# STM8L-FOX_80m_PA_V5_3.net
KiCad netlist of a schematic drawn in EAGLE
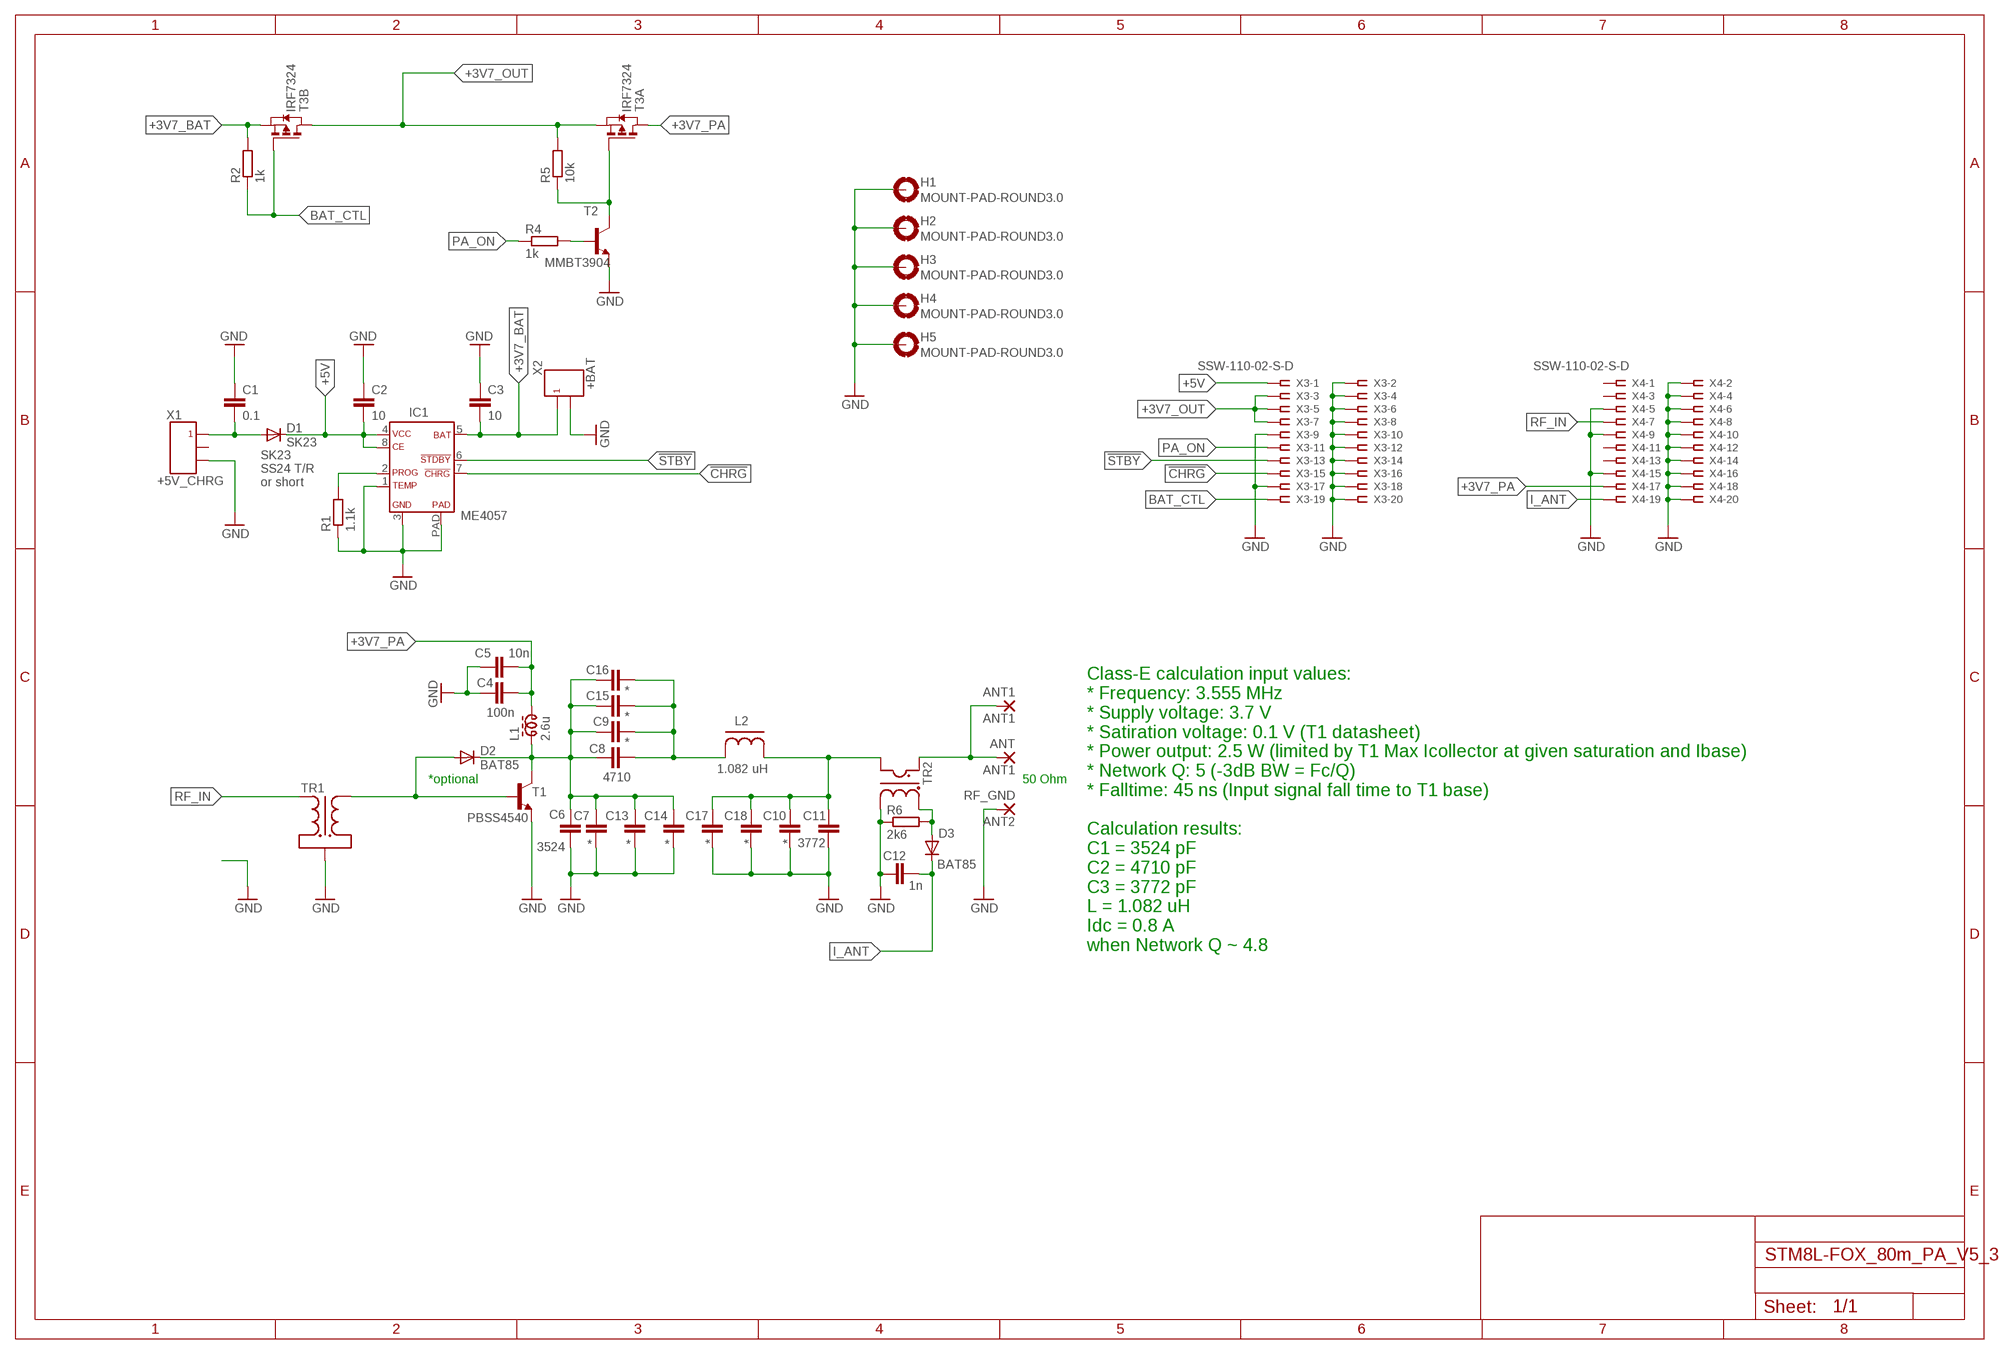
[diagram p0: schematic, sheet 1]

(export (version "E")
  (design (tool "Eeschema 10.0.6"))
  (components
    (comp (ref "ANT")
      (value "ANT1")
      (footprint "eagle-import:2,54_0,8")
      (libsource (lib "eagle-import") (part "WIREPAD2,54/0,8"))
    )
    (comp (ref "ANT1")
      (value "ANT1")
      (footprint "eagle-import:2,54_0,8")
      (libsource (lib "eagle-import") (part "WIREPAD2,54/0,8"))
    )
    (comp (ref "C1")
      (value "0.1")
      (footprint "eagle-import:C1206K")
      (libsource (lib "eagle-import") (part "C-EUC1206K"))
    )
    (comp (ref "C2")
      (value "10")
      (footprint "eagle-import:C1206K")
      (libsource (lib "eagle-import") (part "C-EUC1206K"))
    )
    (comp (ref "C3")
      (value "10")
      (footprint "eagle-import:C1206K")
      (libsource (lib "eagle-import") (part "C-EUC1206K"))
    )
    (comp (ref "C4")
      (value "100n")
      (footprint "eagle-import:C1206K")
      (libsource (lib "eagle-import") (part "C-EUC1206K"))
    )
    (comp (ref "C5")
      (value "10n")
      (footprint "eagle-import:C1206K")
      (libsource (lib "eagle-import") (part "C-EUC1206K"))
    )
    (comp (ref "C6")
      (value "3524")
      (footprint "eagle-import:C1206K")
      (libsource (lib "eagle-import") (part "C-EUC1206K"))
    )
    (comp (ref "C7")
      (value "*")
      (footprint "eagle-import:C1206K")
      (libsource (lib "eagle-import") (part "C-EUC1206K"))
    )
    (comp (ref "C8")
      (value "4710")
      (footprint "eagle-import:C1206K")
      (libsource (lib "eagle-import") (part "C-EUC1206K"))
    )
    (comp (ref "C9")
      (value "*")
      (footprint "eagle-import:C1206K")
      (libsource (lib "eagle-import") (part "C-EUC1206K"))
    )
    (comp (ref "C10")
      (value "*")
      (footprint "eagle-import:C1206K")
      (libsource (lib "eagle-import") (part "C-EUC1206K"))
    )
    (comp (ref "C11")
      (value "3772")
      (footprint "eagle-import:C1206K")
      (libsource (lib "eagle-import") (part "C-EUC1206K"))
    )
    (comp (ref "C12")
      (value "1n")
      (footprint "eagle-import:C1206K")
      (libsource (lib "eagle-import") (part "C-EUC1206K"))
    )
    (comp (ref "C13")
      (value "*")
      (footprint "eagle-import:C1206K")
      (libsource (lib "eagle-import") (part "C-EUC1206K"))
    )
    (comp (ref "C14")
      (value "*")
      (footprint "eagle-import:C1206K")
      (libsource (lib "eagle-import") (part "C-EUC1206K"))
    )
    (comp (ref "C15")
      (value "*")
      (footprint "eagle-import:C1206K")
      (libsource (lib "eagle-import") (part "C-EUC1206K"))
    )
    (comp (ref "C16")
      (value "*")
      (footprint "eagle-import:C1206K")
      (libsource (lib "eagle-import") (part "C-EUC1206K"))
    )
    (comp (ref "C17")
      (value "*")
      (footprint "eagle-import:C1206K")
      (libsource (lib "eagle-import") (part "C-EUC1206K"))
    )
    (comp (ref "C18")
      (value "*")
      (footprint "eagle-import:C1206K")
      (libsource (lib "eagle-import") (part "C-EUC1206K"))
    )
    (comp (ref "D1")
      (value "SK23")
      (footprint "eagle-import:DO-214AC")
      (libsource (lib "eagle-import") (part "DIODE-DO-214AC"))
    )
    (comp (ref "D2")
      (value "BAT85")
      (footprint "eagle-import:DO34-7")
      (libsource (lib "eagle-import") (part "BAT81"))
    )
    (comp (ref "D3")
      (value "BAT85")
      (footprint "eagle-import:DO34-7")
      (libsource (lib "eagle-import") (part "BAT81"))
    )
    (comp (ref "H1")
      (value "MOUNT-PAD-ROUND3.0")
      (footprint "eagle-import:3,0-PAD")
      (libsource (lib "eagle-import") (part "MOUNT-PAD-ROUND3.0"))
    )
    (comp (ref "H2")
      (value "MOUNT-PAD-ROUND3.0")
      (footprint "eagle-import:3,0-PAD")
      (libsource (lib "eagle-import") (part "MOUNT-PAD-ROUND3.0"))
    )
    (comp (ref "H3")
      (value "MOUNT-PAD-ROUND3.0")
      (footprint "eagle-import:3,0-PAD")
      (libsource (lib "eagle-import") (part "MOUNT-PAD-ROUND3.0"))
    )
    (comp (ref "H4")
      (value "MOUNT-PAD-ROUND3.0")
      (footprint "eagle-import:3,0-PAD")
      (libsource (lib "eagle-import") (part "MOUNT-PAD-ROUND3.0"))
    )
    (comp (ref "H5")
      (value "MOUNT-PAD-ROUND3.0")
      (footprint "eagle-import:3,0-PAD")
      (libsource (lib "eagle-import") (part "MOUNT-PAD-ROUND3.0"))
    )
    (comp (ref "IC1")
      (value "ME4057A")
      (footprint "eagle-import:SOP08-PP")
      (libsource (lib "eagle-import") (part "ME4057"))
    )
    (comp (ref "L1")
      (value "2.6u")
      (footprint "eagle-import:ZD6-3W")
      (libsource (lib "eagle-import") (part "ZD60820513"))
    )
    (comp (ref "L2")
      (value "1.082 uH")
      (footprint "eagle-import:T68_COIL")
      (libsource (lib "eagle-import") (part "T68_COIL"))
    )
    (comp (ref "R1")
      (value "1.1k")
      (footprint "eagle-import:R1206")
      (libsource (lib "eagle-import") (part "R-EU_R1206"))
    )
    (comp (ref "R2")
      (value "1k")
      (footprint "eagle-import:R1206")
      (libsource (lib "eagle-import") (part "R-EU_R1206"))
    )
    (comp (ref "R4")
      (value "1k")
      (footprint "eagle-import:R1206")
      (libsource (lib "eagle-import") (part "R-EU_R1206"))
    )
    (comp (ref "R5")
      (value "10k")
      (footprint "eagle-import:R1206")
      (libsource (lib "eagle-import") (part "R-EU_R1206"))
    )
    (comp (ref "R6")
      (value "2k6")
      (footprint "eagle-import:R1206")
      (libsource (lib "eagle-import") (part "R-EU_R1206"))
    )
    (comp (ref "RF_GND")
      (value "ANT2")
      (footprint "eagle-import:2,54_0,8")
      (libsource (lib "eagle-import") (part "WIREPAD2,54/0,8"))
    )
    (comp (ref "T1")
      (value "PBSS4540")
      (footprint "eagle-import:SOT223")
      (libsource (lib "eagle-import") (part "PBSS4540"))
    )
    (comp (ref "T2")
      (value "MMBT3904")
      (footprint "eagle-import:SOT23-BEC")
      (libsource (lib "eagle-import") (part "-NPN-SOT23-BECMMBT3904LT1"))
    )
    (comp (ref "T3")
      (value "IRF7324")
      (footprint "eagle-import:SO8")
      (libsource (lib "eagle-import") (part "PMOS2SO8"))
    )
    (comp (ref "TR1")
      (value "K7X4X2_TRANS_1V1")
      (footprint "eagle-import:K7X4X2_TRANS_1V1")
      (libsource (lib "eagle-import") (part "K7X4X2_TRANS_1V1"))
    )
    (comp (ref "TR2")
      (value "K7X4X2_TRANS_CURRENT")
      (footprint "eagle-import:K7X4X2_TRANS_CURRENT")
      (libsource (lib "eagle-import") (part "K7X4X2_TRANS_CURRENT"))
    )
    (comp (ref "X1")
      (value "+5V_CHRG")
      (footprint "eagle-import:A2501WR-3P")
      (libsource (lib "eagle-import") (part "A2501WR-3P"))
    )
    (comp (ref "X2")
      (value "+BAT")
      (footprint "eagle-import:A2501WR-2P")
      (libsource (lib "eagle-import") (part "A2501WR-2P"))
    )
    (comp (ref "X3")
      (value "SSW-110-02-S-D")
      (footprint "eagle-import:SSW-110-02-S-D")
      (libsource (lib "eagle-import") (part "SSW-110-02-S-D"))
    )
    (comp (ref "X4")
      (value "SSW-110-02-S-D")
      (footprint "eagle-import:SSW-110-02-S-D")
      (libsource (lib "eagle-import") (part "SSW-110-02-S-D"))
    )
  )
  (nets
    (net (code "1") (name "+3V7_BAT") (class "Default")
      (node (ref "C3") (pin "2") (pinfunction "2_2") (pintype "passive"))
      (node (ref "IC1") (pin "5") (pinfunction "P$5_5") (pintype "input"))
      (node (ref "R2") (pin "2") (pinfunction "2_2") (pintype "passive"))
      (node (ref "T3") (pin "3") (pinfunction "S_3") (pintype "passive"))
      (node (ref "X2") (pin "P$1") (pinfunction "P$1_P$1") (pintype "bidirectional"))
    )
    (net (code "2") (name "+3V7_OUT") (class "Default")
      (node (ref "R5") (pin "2") (pinfunction "2_2") (pintype "passive"))
      (node (ref "T3") (pin "1") (pinfunction "S_1") (pintype "passive"))
      (node (ref "T3") (pin "5") (pinfunction "D_5") (pintype "passive"))
      (node (ref "T3") (pin "6") (pinfunction "D_6") (pintype "passive"))
      (node (ref "X3") (pin "3") (pinfunction "1_3") (pintype "passive"))
      (node (ref "X3") (pin "5") (pinfunction "1_5") (pintype "passive"))
      (node (ref "X3") (pin "7") (pinfunction "1_7") (pintype "passive"))
    )
    (net (code "3") (name "+3V7_PA") (class "Default")
      (node (ref "C4") (pin "2") (pinfunction "2_2") (pintype "passive"))
      (node (ref "C5") (pin "1") (pinfunction "1_1") (pintype "passive"))
      (node (ref "L1") (pin "2") (pinfunction "2_2") (pintype "passive"))
      (node (ref "T3") (pin "7") (pinfunction "D_7") (pintype "passive"))
      (node (ref "T3") (pin "8") (pinfunction "D_8") (pintype "passive"))
      (node (ref "X4") (pin "17") (pinfunction "1_17") (pintype "passive"))
    )
    (net (code "4") (name "+5V") (class "Default")
      (node (ref "C2") (pin "2") (pinfunction "2_2") (pintype "passive"))
      (node (ref "D1") (pin "C") (pinfunction "C_C") (pintype "passive"))
      (node (ref "IC1") (pin "4") (pinfunction "P$4_4") (pintype "input"))
      (node (ref "IC1") (pin "8") (pinfunction "P$8_8") (pintype "input"))
      (node (ref "X3") (pin "1") (pinfunction "1_1") (pintype "passive"))
    )
    (net (code "5") (name "/~{CHRG}") (class "Default")
      (node (ref "IC1") (pin "7") (pinfunction "P$7_7") (pintype "output"))
      (node (ref "X3") (pin "15") (pinfunction "1_15") (pintype "passive"))
    )
    (net (code "6") (name "/~{STBY}") (class "Default")
      (node (ref "IC1") (pin "6") (pinfunction "P$6_6") (pintype "output"))
      (node (ref "X3") (pin "13") (pinfunction "1_13") (pintype "passive"))
    )
    (net (code "7") (name "BAT_CTL") (class "Default")
      (node (ref "R2") (pin "1") (pinfunction "1_1") (pintype "passive"))
      (node (ref "T3") (pin "4") (pinfunction "G_4") (pintype "passive"))
      (node (ref "X3") (pin "19") (pinfunction "1_19") (pintype "passive"))
    )
    (net (code "8") (name "GND") (class "Default")
      (node (ref "C1") (pin "1") (pinfunction "1_1") (pintype "passive"))
      (node (ref "C10") (pin "2") (pinfunction "2_2") (pintype "passive"))
      (node (ref "C11") (pin "2") (pinfunction "2_2") (pintype "passive"))
      (node (ref "C12") (pin "1") (pinfunction "1_1") (pintype "passive"))
      (node (ref "C13") (pin "2") (pinfunction "2_2") (pintype "passive"))
      (node (ref "C14") (pin "2") (pinfunction "2_2") (pintype "passive"))
      (node (ref "C17") (pin "2") (pinfunction "2_2") (pintype "passive"))
      (node (ref "C18") (pin "2") (pinfunction "2_2") (pintype "passive"))
      (node (ref "C2") (pin "1") (pinfunction "1_1") (pintype "passive"))
      (node (ref "C3") (pin "1") (pinfunction "1_1") (pintype "passive"))
      (node (ref "C4") (pin "1") (pinfunction "1_1") (pintype "passive"))
      (node (ref "C5") (pin "2") (pinfunction "2_2") (pintype "passive"))
      (node (ref "C6") (pin "2") (pinfunction "2_2") (pintype "passive"))
      (node (ref "C7") (pin "2") (pinfunction "2_2") (pintype "passive"))
      (node (ref "H1") (pin "B3,0") (pinfunction "MOUNT_B3,0") (pintype "passive"))
      (node (ref "H2") (pin "B3,0") (pinfunction "MOUNT_B3,0") (pintype "passive"))
      (node (ref "H3") (pin "B3,0") (pinfunction "MOUNT_B3,0") (pintype "passive"))
      (node (ref "H4") (pin "B3,0") (pinfunction "MOUNT_B3,0") (pintype "passive"))
      (node (ref "H5") (pin "B3,0") (pinfunction "MOUNT_B3,0") (pintype "passive"))
      (node (ref "IC1") (pin "1") (pinfunction "P$1_1") (pintype "input"))
      (node (ref "IC1") (pin "3") (pinfunction "P$3_3") (pintype "input"))
      (node (ref "IC1") (pin "PAD") (pinfunction "P$9_PAD") (pintype "passive"))
      (node (ref "R1") (pin "1") (pinfunction "1_1") (pintype "passive"))
      (node (ref "R6") (pin "1") (pinfunction "1_1") (pintype "passive"))
      (node (ref "RF_GND") (pin "1") (pinfunction "P_1") (pintype "passive"))
      (node (ref "T1") (pin "3") (pinfunction "E_3") (pintype "passive"))
      (node (ref "T2") (pin "E") (pinfunction "E_E") (pintype "passive"))
      (node (ref "TR1") (pin "P$1") (pinfunction "P$1_P$1") (pintype "input"))
      (node (ref "TR2") (pin "P$4") (pinfunction "P$4_P$4") (pintype "input"))
      (node (ref "X1") (pin "P$3") (pinfunction "P$3_P$3") (pintype "bidirectional"))
      (node (ref "X2") (pin "P$2") (pinfunction "P$2_P$2") (pintype "bidirectional"))
      (node (ref "X3") (pin "10") (pinfunction "1_10") (pintype "passive"))
      (node (ref "X3") (pin "12") (pinfunction "1_12") (pintype "passive"))
      (node (ref "X3") (pin "14") (pinfunction "1_14") (pintype "passive"))
      (node (ref "X3") (pin "16") (pinfunction "1_16") (pintype "passive"))
      (node (ref "X3") (pin "17") (pinfunction "1_17") (pintype "passive"))
      (node (ref "X3") (pin "18") (pinfunction "1_18") (pintype "passive"))
      (node (ref "X3") (pin "2") (pinfunction "1_2") (pintype "passive"))
      (node (ref "X3") (pin "20") (pinfunction "1_20") (pintype "passive"))
      (node (ref "X3") (pin "4") (pinfunction "1_4") (pintype "passive"))
      (node (ref "X3") (pin "6") (pinfunction "1_6") (pintype "passive"))
      (node (ref "X3") (pin "8") (pinfunction "1_8") (pintype "passive"))
      (node (ref "X3") (pin "9") (pinfunction "1_9") (pintype "passive"))
      (node (ref "X4") (pin "10") (pinfunction "1_10") (pintype "passive"))
      (node (ref "X4") (pin "12") (pinfunction "1_12") (pintype "passive"))
      (node (ref "X4") (pin "14") (pinfunction "1_14") (pintype "passive"))
      (node (ref "X4") (pin "15") (pinfunction "1_15") (pintype "passive"))
      (node (ref "X4") (pin "16") (pinfunction "1_16") (pintype "passive"))
      (node (ref "X4") (pin "18") (pinfunction "1_18") (pintype "passive"))
      (node (ref "X4") (pin "2") (pinfunction "1_2") (pintype "passive"))
      (node (ref "X4") (pin "20") (pinfunction "1_20") (pintype "passive"))
      (node (ref "X4") (pin "4") (pinfunction "1_4") (pintype "passive"))
      (node (ref "X4") (pin "5") (pinfunction "1_5") (pintype "passive"))
      (node (ref "X4") (pin "6") (pinfunction "1_6") (pintype "passive"))
      (node (ref "X4") (pin "8") (pinfunction "1_8") (pintype "passive"))
      (node (ref "X4") (pin "9") (pinfunction "1_9") (pintype "passive"))
    )
    (net (code "9") (name "I_ANT") (class "Default")
      (node (ref "C12") (pin "2") (pinfunction "2_2") (pintype "passive"))
      (node (ref "D3") (pin "C") (pinfunction "C_C") (pintype "passive"))
      (node (ref "X4") (pin "19") (pinfunction "1_19") (pintype "passive"))
    )
    (net (code "10") (name "Net-(ANT-P)") (class "Default")
      (node (ref "ANT") (pin "1") (pinfunction "P_1") (pintype "passive"))
      (node (ref "ANT1") (pin "1") (pinfunction "P_1") (pintype "passive"))
      (node (ref "TR2") (pin "P$1") (pinfunction "P$1_P$1") (pintype "input"))
    )
    (net (code "11") (name "Net-(C1-Pad2)") (class "Default")
      (node (ref "C1") (pin "2") (pinfunction "2_2") (pintype "passive"))
      (node (ref "D1") (pin "A") (pinfunction "A_A") (pintype "passive"))
      (node (ref "X1") (pin "P$1") (pinfunction "P$1_P$1") (pintype "bidirectional"))
    )
    (net (code "12") (name "Net-(C10-Pad1)") (class "Default")
      (node (ref "C10") (pin "1") (pinfunction "1_1") (pintype "passive"))
      (node (ref "C11") (pin "1") (pinfunction "1_1") (pintype "passive"))
      (node (ref "C17") (pin "1") (pinfunction "1_1") (pintype "passive"))
      (node (ref "C18") (pin "1") (pinfunction "1_1") (pintype "passive"))
      (node (ref "L2") (pin "P$2") (pinfunction "P$2_P$2") (pintype "input"))
      (node (ref "TR2") (pin "P$2") (pinfunction "P$2_P$2") (pintype "input"))
    )
    (net (code "13") (name "Net-(C13-Pad1)") (class "Default")
      (node (ref "C13") (pin "1") (pinfunction "1_1") (pintype "passive"))
      (node (ref "C14") (pin "1") (pinfunction "1_1") (pintype "passive"))
      (node (ref "C15") (pin "1") (pinfunction "1_1") (pintype "passive"))
      (node (ref "C16") (pin "1") (pinfunction "1_1") (pintype "passive"))
      (node (ref "C6") (pin "1") (pinfunction "1_1") (pintype "passive"))
      (node (ref "C7") (pin "1") (pinfunction "1_1") (pintype "passive"))
      (node (ref "C8") (pin "1") (pinfunction "1_1") (pintype "passive"))
      (node (ref "C9") (pin "1") (pinfunction "1_1") (pintype "passive"))
      (node (ref "D2") (pin "C") (pinfunction "C_C") (pintype "passive"))
      (node (ref "L1") (pin "1") (pinfunction "1_1") (pintype "passive"))
      (node (ref "T1") (pin "2") (pinfunction "C_2") (pintype "passive"))
      (node (ref "T1") (pin "4") (pinfunction "C_4") (pintype "passive"))
    )
    (net (code "14") (name "Net-(C15-Pad2)") (class "Default")
      (node (ref "C15") (pin "2") (pinfunction "2_2") (pintype "passive"))
      (node (ref "C16") (pin "2") (pinfunction "2_2") (pintype "passive"))
      (node (ref "C8") (pin "2") (pinfunction "2_2") (pintype "passive"))
      (node (ref "C9") (pin "2") (pinfunction "2_2") (pintype "passive"))
      (node (ref "L2") (pin "P$1") (pinfunction "P$1_P$1") (pintype "input"))
    )
    (net (code "15") (name "Net-(D3-PadA)") (class "Default")
      (node (ref "D3") (pin "A") (pinfunction "A_A") (pintype "passive"))
      (node (ref "R6") (pin "2") (pinfunction "2_2") (pintype "passive"))
      (node (ref "TR2") (pin "P$3") (pinfunction "P$3_P$3") (pintype "input"))
    )
    (net (code "16") (name "Net-(IC1-P$2)") (class "Default")
      (node (ref "IC1") (pin "2") (pinfunction "P$2_2") (pintype "input"))
      (node (ref "R1") (pin "2") (pinfunction "2_2") (pintype "passive"))
    )
    (net (code "17") (name "Net-(R4-Pad2)") (class "Default")
      (node (ref "R4") (pin "2") (pinfunction "2_2") (pintype "passive"))
      (node (ref "T2") (pin "B") (pinfunction "B_B") (pintype "passive"))
    )
    (net (code "18") (name "Net-(T1-B)") (class "Default")
      (node (ref "D2") (pin "A") (pinfunction "A_A") (pintype "passive"))
      (node (ref "T1") (pin "1") (pinfunction "B_1") (pintype "passive"))
      (node (ref "TR1") (pin "P$3") (pinfunction "P$3_P$3") (pintype "input"))
    )
    (net (code "19") (name "Net-(T3A-G)") (class "Default")
      (node (ref "R5") (pin "1") (pinfunction "1_1") (pintype "passive"))
      (node (ref "T2") (pin "C") (pinfunction "C_C") (pintype "passive"))
      (node (ref "T3") (pin "2") (pinfunction "G_2") (pintype "passive"))
    )
    (net (code "20") (name "PA_ON") (class "Default")
      (node (ref "R4") (pin "1") (pinfunction "1_1") (pintype "passive"))
      (node (ref "X3") (pin "11") (pinfunction "1_11") (pintype "passive"))
    )
    (net (code "21") (name "RF_IN") (class "Default")
      (node (ref "TR1") (pin "P$2") (pinfunction "P$2_P$2") (pintype "input"))
      (node (ref "X4") (pin "7") (pinfunction "1_7") (pintype "passive"))
    )
    (net (code "22") (name "unconnected-(L2-PadP$3)") (class "Default")
      (node (ref "L2") (pin "P$3") (pinfunction "P$3_P$3") (pintype "no_connect"))
    )
    (net (code "23") (name "unconnected-(L2-PadP$4)") (class "Default")
      (node (ref "L2") (pin "P$4") (pinfunction "P$4_P$4") (pintype "no_connect"))
    )
    (net (code "24") (name "unconnected-(TR1-PadP$4)") (class "Default")
      (node (ref "TR1") (pin "P$4") (pinfunction "P$4_P$4") (pintype "no_connect"))
    )
    (net (code "25") (name "unconnected-(TR1-PadP$5)") (class "Default")
      (node (ref "TR1") (pin "P$5") (pinfunction "P$5_P$5") (pintype "no_connect"))
    )
    (net (code "26") (name "unconnected-(X1-PadP$2)") (class "Default")
      (node (ref "X1") (pin "P$2") (pinfunction "P$2_P$2") (pintype "bidirectional"))
    )
    (net (code "27") (name "unconnected-(X4-Pad1)") (class "Default")
      (node (ref "X4") (pin "1") (pinfunction "1_1") (pintype "passive"))
    )
    (net (code "28") (name "unconnected-(X4C-1-Pad11)") (class "Default")
      (node (ref "X4") (pin "11") (pinfunction "1_11") (pintype "passive"))
    )
    (net (code "29") (name "unconnected-(X4E-1-Pad13)") (class "Default")
      (node (ref "X4") (pin "13") (pinfunction "1_13") (pintype "passive"))
    )
    (net (code "30") (name "unconnected-(X4N-1-Pad3)") (class "Default")
      (node (ref "X4") (pin "3") (pinfunction "1_3") (pintype "passive"))
    )
  )
)
